# IRF.net
KiCad netlist of a schematic drawn in EAGLE
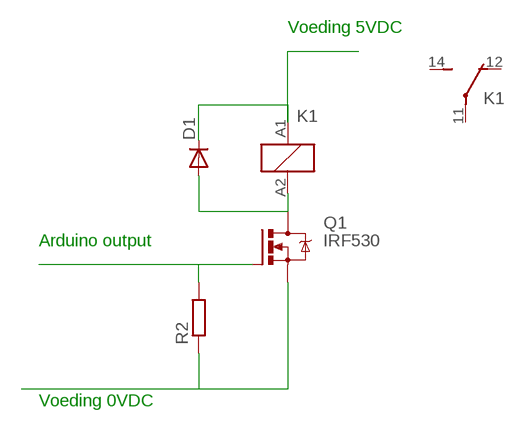
[diagram p0: schematic, sheet 1]

(export (version "E")
  (design (tool "Eeschema 10.0.6"))
  (components
    (comp (ref "D1")
      (value "1N4148DO35-7")
      (footprint "eagle-import:DO35-7")
      (libsource (lib "eagle-import") (part "1N4148DO35-7"))
    )
    (comp (ref "K1")
      (value "FINDER-30.22")
      (footprint "eagle-import:FINDER-30.22")
      (libsource (lib "eagle-import") (part "FINDER-30.22"))
    )
    (comp (ref "Q1")
      (value "IRF530")
      (footprint "eagle-import:TO220BV")
      (libsource (lib "eagle-import") (part "IRF530"))
    )
    (comp (ref "R2")
      (value "R-EU_0309/12")
      (footprint "eagle-import:0309_12")
      (libsource (lib "eagle-import") (part "R-EU_0309/12"))
    )
  )
  (nets
    (net (code "1") (name "Net-(K1C-1)") (class "Default")
      (node (ref "D1") (pin "C") (pinfunction "C_C") (pintype "passive"))
      (node (ref "K1") (pin "A1") (pinfunction "1_A1") (pintype "passive"))
    )
    (net (code "2") (name "Net-(K1C-2)") (class "Default")
      (node (ref "D1") (pin "A") (pinfunction "A_A") (pintype "passive"))
      (node (ref "K1") (pin "A2") (pinfunction "2_A2") (pintype "passive"))
      (node (ref "Q1") (pin "D") (pinfunction "D_D") (pintype "passive"))
    )
    (net (code "3") (name "Net-(Q1-PadG)") (class "Default")
      (node (ref "Q1") (pin "G") (pinfunction "G_G") (pintype "passive"))
      (node (ref "R2") (pin "2") (pinfunction "2_2") (pintype "passive"))
    )
    (net (code "4") (name "Net-(Q1-PadS)") (class "Default")
      (node (ref "Q1") (pin "S") (pinfunction "S_S") (pintype "passive"))
      (node (ref "R2") (pin "1") (pinfunction "1_1") (pintype "passive"))
    )
    (net (code "5") (name "unconnected-(K1A-O-Pad12)") (class "Default")
      (node (ref "K1") (pin "12") (pinfunction "O_12") (pintype "passive"))
    )
    (net (code "6") (name "unconnected-(K1A-P-Pad11)") (class "Default")
      (node (ref "K1") (pin "11") (pinfunction "P_11") (pintype "passive"))
    )
    (net (code "7") (name "unconnected-(K1A-S-Pad14)") (class "Default")
      (node (ref "K1") (pin "14") (pinfunction "S_14") (pintype "passive"))
    )
  )
)
